# Power.net
KiCad netlist of a schematic drawn in Altium Designer
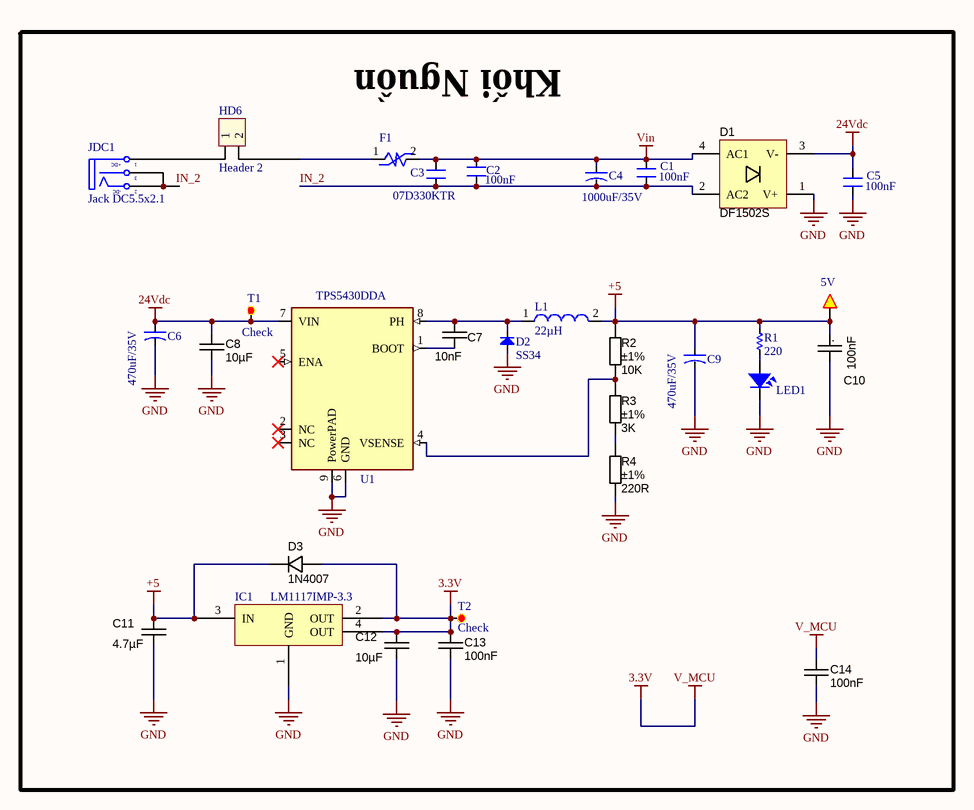
[diagram p0: Power.SchDoc]

(export (version "E")
  (design (tool "Eeschema 10.0.6"))
  (components
    (comp (ref "C1") (value "100nF") (footprint "CN-SMD-1206") (libsource (lib "thu vien 3d") (part "CN")))
    (comp (ref "C2") (value "100nF") (footprint "CN2.5") (libsource (lib "thu vien 3d") (part "CN")))
    (comp (ref "C3") (value "07D330KTR") (footprint "CN2-T") (libsource (lib "thu vien 3d") (part "CN")))
    (comp (ref "C4")
      (value "1000uF/35V")
      (footprint "CA-ALU-5L")
      (description "Capacitor (Semiconductor SIM Model)")
      (fields (field (name "PUBLISHER") "Altium Limited"))
      (libsource (lib "thu vien 3d") (part "CN-ALU-DIP"))
    )
    (comp (ref "C5") (value "100nF") (footprint "CN-SMD-1206") (libsource (lib "thu vien 3d") (part "CN")))
    (comp (ref "C6")
      (value "470uF/35V")
      (footprint "CA-ALU-6.3")
      (description "Capacitor (Semiconductor SIM Model)")
      (fields (field (name "PUBLISHER") "Altium Limited"))
      (libsource (lib "thu vien 3d") (part "CN-ALU-DIP"))
    )
    (comp (ref "C7")
      (value "10nF")
      (footprint "CAPC1608X90N")
      (description "10000pF ±10% 50V Ceramic Capacitor X7R 0603 (1608 Metric)")
      (fields (field (name "TOLERANCE") "±10%"))
      (libsource (lib "SangMV") (part "CAPC_10000pF_0603_50V_10%"))
    )
    (comp (ref "C8")
      (value "10µF")
      (footprint "CAPC2012X135N")
      (description "10µF ±10% 25V Ceramic Capacitor X7R 1206 (3216 Metric)")
      (fields (field (name "TOLERANCE") "±10%") (field (name "MANUFACTURER PART NUMBER") "TMK316AB7106KLHT"))
      (libsource (lib "All Library") (part "CAPC_10uF_0805_X7R_25V_10%"))
    )
    (comp (ref "C9")
      (value "470uF/35V")
      (footprint "CA-ALU-6.3")
      (description "Capacitor (Semiconductor SIM Model)")
      (fields (field (name "PUBLISHER") "Altium Limited"))
      (libsource (lib "thu vien 3d") (part "CN-ALU-DIP"))
    )
    (comp (ref "C10")
      (value "100nF")
      (footprint "CAPC2012X135N")
      (description "0.1µF ±10% 50V Ceramic Capacitor X7R 0805 (2012 Metric)")
      (fields (field (name "TOLERANCE") "±10%") (field (name "MANUFACTURER PART NUMBER") "CL21B104KBFXPJE"))
      (libsource (lib "SangMV") (part "CAPC_100nF_0805_X7R_50V_10%"))
    )
    (comp (ref "C11")
      (value "4.7µF")
      (footprint "CAPC2012X135N")
      (description "4.7µF ±10% 50V Ceramic Capacitor X7R 0805 (2012 Metric)")
      (fields
        (field (name "TOLERANCE") "±10%")
        (field (name "MANUFACTURER PART NUMBER") "CGA4J1X7R1H475K125AE")
      )
      (libsource (lib "All Library") (part "CAPC_4.7uF_0805_X7R_50V_10%"))
    )
    (comp (ref "C12")
      (value "10µF")
      (footprint "CAPC2012X135N")
      (description "4.7µF ±10% 50V Ceramic Capacitor X7R 0805 (2012 Metric)")
      (fields
        (field (name "TOLERANCE") "±10%")
        (field (name "MANUFACTURER PART NUMBER") "CGA4J1X7R1H475K125AE")
      )
      (libsource (lib "All Library") (part "CAPC_4.7uF_0805_X7R_50V_10%"))
    )
    (comp (ref "C13")
      (value "100nF")
      (footprint "CAPC1608X90N")
      (description "0.1µF ±10% 50V Ceramic Capacitor X7R 0603 (1608 Metric)")
      (fields (field (name "TOLERANCE") "±10%"))
      (libsource (lib "All Library") (part "CAPC_100nF_0603_X7R_50V_10%"))
    )
    (comp (ref "C14")
      (value "100nF")
      (footprint "CAPC1608X90N")
      (description "0.1µF ±10% 50V Ceramic Capacitor X7R 0603 (1608 Metric)")
      (fields (field (name "TOLERANCE") "±10%"))
      (libsource (lib "All Library") (part "CAPC_100nF_0603_X7R_50V_10%"))
    )
    (comp (ref "Check1")
      (value "5V")
      (footprint "SMD-2")
      (description "WR-PHD 2.54 mm Angled Socket Header")
      (fields
        (field (name "MANUFACTURER") "Würth Elektronik eiSos GmbH")
        (field (name "PARTNO") "613002143121")
        (field (name "CREATED BY") "Karrer Zheng")
      )
      (libsource (lib "Nichietsuvn") (part "Test"))
    )
    (comp (ref "D1")
      (value "DF1502S")
      (footprint "DIODE_DF_S")
      (description "Bridge Rectifier Single Phase Standard 200V Surface Mount DF-S")
      (libsource (lib "PCB_ESP32_Extern") (part "DIODE_DF1502S"))
    )
    (comp (ref "D2")
      (value "SS34")
      (footprint "DIO-SMD-106")
      (description "Default Diode")
      (fields (field (name "PUBLISHER") "Altium Limited"))
      (libsource (lib "thu vien 3d") (part "Diode SMD"))
    )
    (comp (ref "D3")
      (value "1N4007")
      (footprint "DO-214AC")
      (description "Diode  Standard Rectifier SMD 1000V 1A SMA")
      (libsource (lib "All Library") (part "DIODE_1N4007"))
    )
    (comp (ref "F1") (value "RUEF185") (footprint "RUEF165") (libsource (lib "All Library") (part "RUEF185")))
    (comp (ref "HD6") (value "Header 2") (footprint "Header_2") (libsource (lib "lpson") (part "Header2")))
    (comp (ref "IC1")
      (value "LM1117IMP-3.3")
      (footprint "SOT223")
      (description "Linear Voltage Regulator IC  1 Output  800mA SOT-223")
      (fields
        (field (name "MANUFACTURER") "Texas Instruments")
        (field (name "MANUFACTURER PART NUMBER") "LM1117IMP-3.3/NOPB")
      )
      (libsource (lib "All Library") (part "IC_LM1117IMP-3.3"))
    )
    (comp (ref "JDC1")
      (value "Jack DC5.5x2.1")
      (footprint "DC-IN")
      (description "Cắm")
      (libsource (lib "THU VIEN SCH") (part "Jac_DC"))
    )
    (comp (ref "L1")
      (value "22µH")
      (footprint "IND_COIL_8D43")
      (description "22µH Shielded Wirewound Inductor 950mA 380mOhm Max Nonstandard")
      (libsource (lib "SangMV") (part "INDC_SMD_22uH_8D43"))
    )
    (comp (ref "LED1")
      (value "LED")
      (footprint "LED-0805-Blue")
      (libsource (lib "thu vien 3d") (part "LED SMD"))
    )
    (comp (ref "R1")
      (value "220")
      (footprint "RES-SMD-0603")
      (description "Resistor")
      (fields
        (field (name "MANUFACTURER") "Generic Components")
        (field (name "PUBLISHER") "Altium Hobart Technology Centre")
      )
      (libsource (lib "thu vien 3d") (part "Res-SMD"))
    )
    (comp (ref "R2")
      (value "10K")
      (footprint "RESC1608X55N")
      (fields
        (field (name "MANUFACTURER") "Stackpole Electronics Inc")
        (field (name "MANUFACTURER PART NUMBER") "RMCF0603FT10K0")
        (field (name "TOLERANCE") "±1%")
        (field (name "Comment") "10K_0603_1%")
      )
      (libsource (lib "SangMV") (part "RES_10K_0603_1%"))
    )
    (comp (ref "R3")
      (value "3K")
      (footprint "RESC1608X55N")
      (description "3 kOhms ±1% 0.1W, 1/10W Chip Resistor 0603 (1608 Metric) Automotive AEC-Q200 Thick Film")
      (fields
        (field (name "MANUFACTURER") "Stackpole Electronics Inc")
        (field (name "MANUFACTURER PART NUMBER") "RMCF0603FT3K00")
        (field (name "TOLERANCE") "±1%")
      )
      (libsource (lib "SangMV") (part "RES_3K_0603_1%"))
    )
    (comp (ref "R4")
      (value "220R")
      (footprint "RESC1608X55N")
      (description "220 Ohms ±1% 0.1W, 1/10W Chip Resistor 0603 (1608 Metric) Automotive AEC-Q200 Thick Film")
      (fields
        (field (name "MANUFACTURER") "Stackpole Electronics Inc")
        (field (name "MANUFACTURER PART NUMBER") "RMCF0603FT220R")
        (field (name "TOLERANCE") "±1%")
      )
      (libsource (lib "SangMV") (part "RES_220R_0603_1%"))
    )
    (comp (ref "T1")
      (value "Check")
      (footprint "SMD_1.5")
      (description "WR-PHD 2.54 mm Angled Socket Header")
      (fields
        (field (name "MANUFACTURER") "Würth Elektronik eiSos GmbH")
        (field (name "PARTNO") "613002143121")
        (field (name "CREATED BY") "Karrer Zheng")
      )
      (libsource (lib "All Library") (part "Test"))
    )
    (comp (ref "T2")
      (value "Check")
      (footprint "SMD_1.5")
      (description "WR-PHD 2.54 mm Angled Socket Header")
      (fields
        (field (name "MANUFACTURER") "Würth Elektronik eiSos GmbH")
        (field (name "PARTNO") "613002143121")
        (field (name "CREATED BY") "Karrer Zheng")
      )
      (libsource (lib "All Library") (part "Test"))
    )
    (comp (ref "U1")
      (value "TPS5430DDA")
      (footprint "TPS5430")
      (libsource (lib "Nichietsuvn") (part "TPS5430DDA"))
    )
  )
  (nets
    (net (code "1") (name "+5") (class "Default")
      (node (ref "C10") (pin "1") (pintype "passive"))
      (node (ref "C11") (pin "2") (pintype "passive"))
      (node (ref "C9") (pin "1") (pinfunction "1_1") (pintype "passive"))
      (node (ref "Check1") (pin "1") (pinfunction "1_1") (pintype "passive"))
      (node (ref "D3") (pin "C") (pinfunction "C_C") (pintype "passive"))
      (node (ref "IC1") (pin "3") (pinfunction "IN_3") (pintype "passive"))
      (node (ref "L1") (pin "2") (pinfunction "2_2") (pintype "passive"))
      (node (ref "R1") (pin "1") (pinfunction "1_1") (pintype "passive"))
      (node (ref "R2") (pin "2") (pinfunction "2_2") (pintype "passive"))
    )
    (net (code "2") (name "/IN_2") (class "Default")
      (node (ref "C1") (pin "1") (pinfunction "1_1") (pintype "passive"))
      (node (ref "C2") (pin "1") (pinfunction "1_1") (pintype "passive"))
      (node (ref "C3") (pin "1") (pinfunction "1_1") (pintype "passive"))
      (node (ref "C4") (pin "2") (pinfunction "2_2") (pintype "passive"))
      (node (ref "D1") (pin "2") (pinfunction "AC2_2") (pintype "passive"))
      (node (ref "JDC1") (pin "2") (pinfunction "TN_2") (pintype "passive"))
      (node (ref "JDC1") (pin "3") (pinfunction "S_3") (pintype "power_in"))
    )
    (net (code "3") (name "3.3V") (class "Default")
      (node (ref "C12") (pin "2") (pintype "passive"))
      (node (ref "C13") (pin "1") (pintype "passive"))
      (node (ref "C14") (pin "1") (pintype "passive"))
      (node (ref "D3") (pin "A") (pinfunction "A_A") (pintype "passive"))
      (node (ref "IC1") (pin "2") (pinfunction "OUT_2") (pintype "passive"))
      (node (ref "IC1") (pin "4") (pinfunction "OUT_4") (pintype "passive"))
      (node (ref "T2") (pin "1") (pinfunction "1_1") (pintype "passive"))
    )
    (net (code "4") (name "24Vdc") (class "Default")
      (node (ref "C5") (pin "2") (pinfunction "2_2") (pintype "passive"))
      (node (ref "C6") (pin "1") (pinfunction "1_1") (pintype "passive"))
      (node (ref "C8") (pin "2") (pintype "passive"))
      (node (ref "D1") (pin "3") (pinfunction "V-_3") (pintype "passive"))
      (node (ref "T1") (pin "1") (pinfunction "1_1") (pintype "passive"))
      (node (ref "U1") (pin "7") (pinfunction "VIN_7") (pintype "power_in"))
    )
    (net (code "5") (name "GND") (class "Default")
      (node (ref "C10") (pin "2") (pintype "passive"))
      (node (ref "C11") (pin "1") (pintype "passive"))
      (node (ref "C12") (pin "1") (pintype "passive"))
      (node (ref "C13") (pin "2") (pintype "passive"))
      (node (ref "C14") (pin "2") (pintype "passive"))
      (node (ref "C5") (pin "1") (pinfunction "1_1") (pintype "passive"))
      (node (ref "C6") (pin "2") (pinfunction "2_2") (pintype "passive"))
      (node (ref "C8") (pin "1") (pintype "passive"))
      (node (ref "C9") (pin "2") (pinfunction "2_2") (pintype "passive"))
      (node (ref "D1") (pin "1") (pinfunction "V+_1") (pintype "passive"))
      (node (ref "D2") (pin "1") (pinfunction "A_1") (pintype "passive"))
      (node (ref "IC1") (pin "1") (pinfunction "GND_1") (pintype "passive"))
      (node (ref "LED1") (pin "2") (pinfunction "2_2") (pintype "passive"))
      (node (ref "R4") (pin "1") (pinfunction "1_1") (pintype "passive"))
      (node (ref "U1") (pin "6") (pinfunction "GND_6") (pintype "power_in"))
      (node (ref "U1") (pin "9") (pinfunction "PowerPAD_9") (pintype "power_in"))
    )
    (net (code "6") (name "Net-(D2-K)") (class "Default")
      (node (ref "C7") (pin "2") (pintype "passive"))
      (node (ref "D2") (pin "2") (pinfunction "K_2") (pintype "passive"))
      (node (ref "L1") (pin "1") (pinfunction "1_1") (pintype "passive"))
      (node (ref "U1") (pin "8") (pinfunction "PH_8") (pintype "input"))
    )
    (net (code "7") (name "Net-(F1-Pad1)") (class "Default")
      (node (ref "F1") (pin "1") (pinfunction "1_1") (pintype "passive"))
      (node (ref "HD6") (pin "2") (pinfunction "2_2") (pintype "passive"))
    )
    (net (code "8") (name "Net-(JDC1-T)") (class "Default")
      (node (ref "HD6") (pin "1") (pinfunction "1_1") (pintype "passive"))
      (node (ref "JDC1") (pin "1") (pinfunction "T_1") (pintype "passive"))
    )
    (net (code "9") (name "Net-(LED1-Pad1)") (class "Default")
      (node (ref "LED1") (pin "1") (pinfunction "1_1") (pintype "passive"))
      (node (ref "R1") (pin "2") (pinfunction "2_2") (pintype "passive"))
    )
    (net (code "10") (name "Net-(R3-Pad1)") (class "Default")
      (node (ref "R3") (pin "1") (pinfunction "1_1") (pintype "passive"))
      (node (ref "R4") (pin "2") (pinfunction "2_2") (pintype "passive"))
    )
    (net (code "11") (name "Net-(U1-BOOT)") (class "Default")
      (node (ref "C7") (pin "1") (pintype "passive"))
      (node (ref "U1") (pin "1") (pinfunction "BOOT_1") (pintype "output"))
    )
    (net (code "12") (name "Net-(U1-VSENSE)") (class "Default")
      (node (ref "R2") (pin "1") (pinfunction "1_1") (pintype "passive"))
      (node (ref "R3") (pin "2") (pinfunction "2_2") (pintype "passive"))
      (node (ref "U1") (pin "4") (pinfunction "VSENSE_4") (pintype "input"))
    )
    (net (code "13") (name "Vin") (class "Default")
      (node (ref "C1") (pin "2") (pinfunction "2_2") (pintype "passive"))
      (node (ref "C2") (pin "2") (pinfunction "2_2") (pintype "passive"))
      (node (ref "C3") (pin "2") (pinfunction "2_2") (pintype "passive"))
      (node (ref "C4") (pin "1") (pinfunction "1_1") (pintype "passive"))
      (node (ref "D1") (pin "4") (pinfunction "AC1_4") (pintype "passive"))
      (node (ref "F1") (pin "2") (pinfunction "2_2") (pintype "passive"))
    )
    (net (code "14") (name "unconnected-(U1-ENA-Pad5)") (class "Default")
      (node (ref "U1") (pin "5") (pinfunction "ENA_5") (pintype "input+no_connect"))
    )
    (net (code "15") (name "unconnected-(U1-NC-Pad2)") (class "Default")
      (node (ref "U1") (pin "2") (pinfunction "NC_2") (pintype "passive+no_connect"))
    )
    (net (code "16") (name "unconnected-(U1-NC-Pad3)") (class "Default")
      (node (ref "U1") (pin "3") (pinfunction "NC_3") (pintype "passive+no_connect"))
    )
  )
)
